# SCH_Bunny-Blinky_2025-12-06.net
KiCad netlist of a schematic drawn in EasyEDA
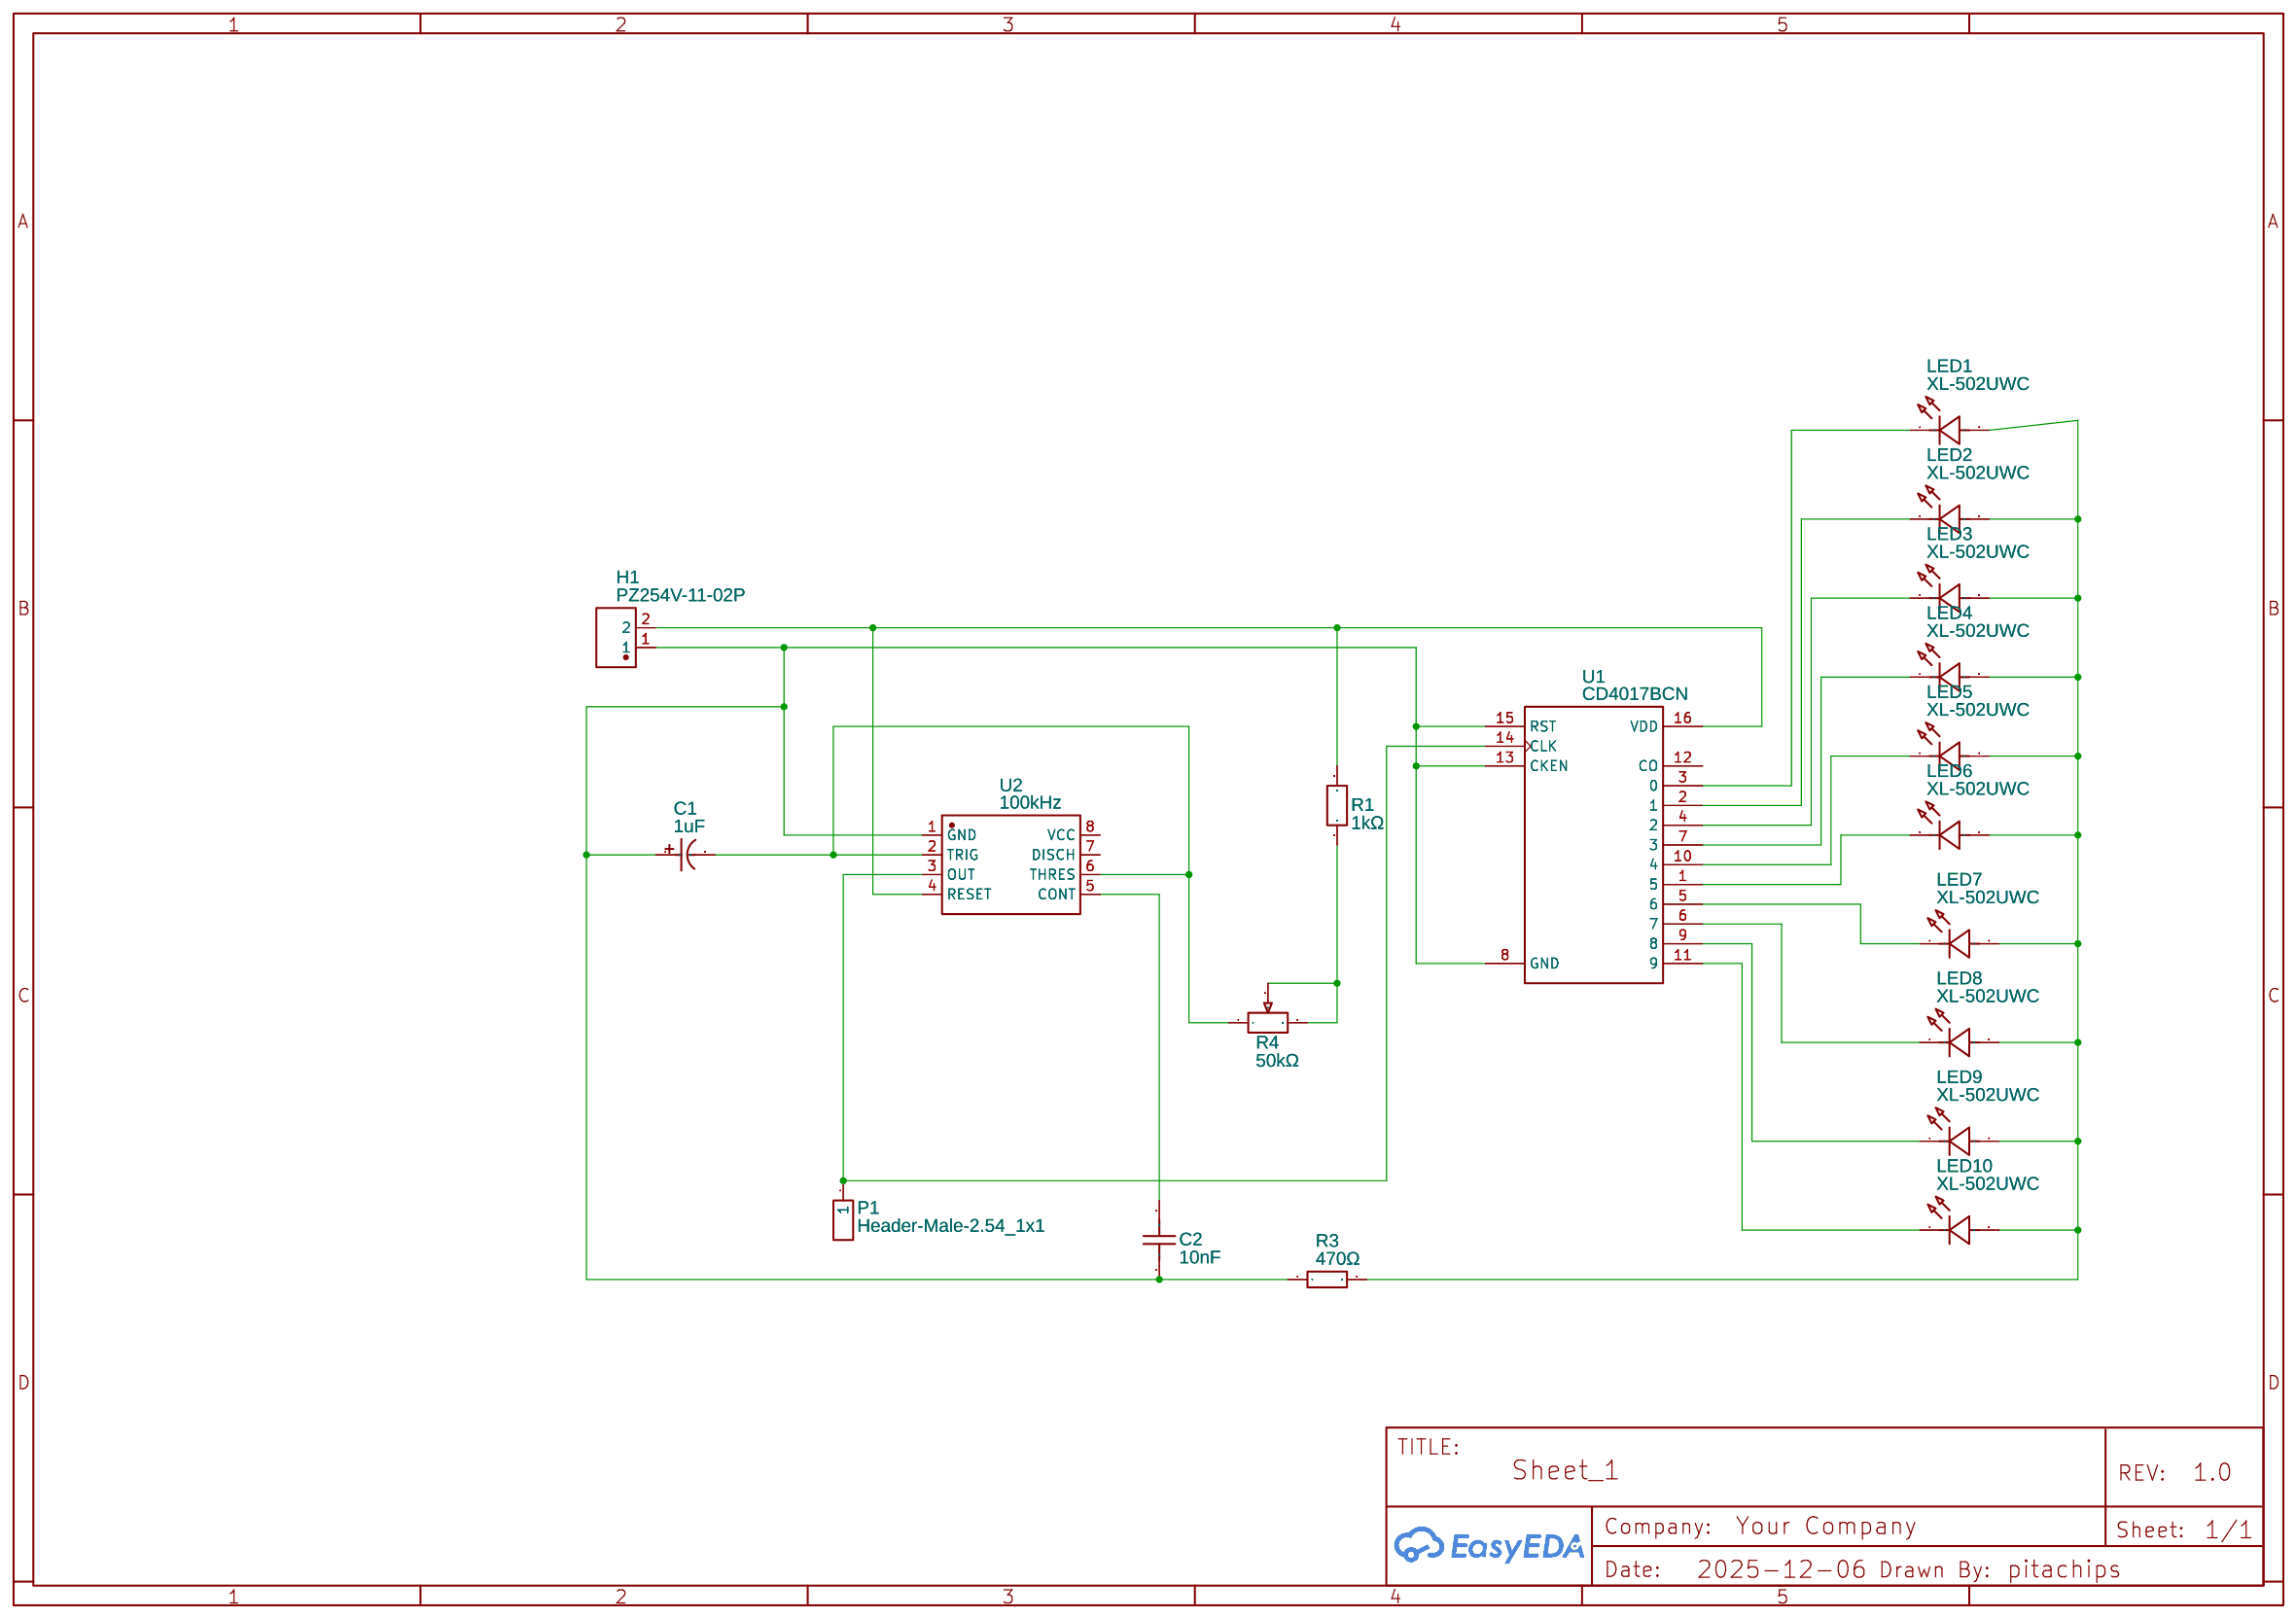
[diagram p0: schematic sheet]

(export (version "E")
  (design (tool "Eeschema 10.0.6"))
  (components
    (comp (ref "C1")
      (value "1uF")
      (fields (field (name "Manufacturer Part") "KF010M050C110A") (field (name "Manufacturer") "CapXon(丰宾)"))
      (libsource (lib "") (part "KF010M050C110A"))
    )
    (comp (ref "C2")
      (value "10nF")
      (fields (field (name "Manufacturer Part") "N09F1B103MN0B0S0N0") (field (name "Manufacturer") "STE(松田)"))
      (libsource (lib "") (part "N09F1B103MN0B0S0N0"))
    )
    (comp (ref "H1")
      (value "PZ254V-11-02P")
      (fields (field (name "Manufacturer") "XFCN(兴飞)"))
      (libsource (lib "") (part "PZ254V-11-02P"))
    )
    (comp (ref "LED1")
      (value "XL-502UWC")
      (fields (field (name "Manufacturer") "XINGLIGHT(成兴光)"))
      (libsource (lib "") (part "XL-502UWC"))
    )
    (comp (ref "LED2")
      (value "XL-502UWC")
      (fields (field (name "Manufacturer") "XINGLIGHT(成兴光)"))
      (libsource (lib "") (part "XL-502UWC"))
    )
    (comp (ref "LED3")
      (value "XL-502UWC")
      (fields (field (name "Manufacturer") "XINGLIGHT(成兴光)"))
      (libsource (lib "") (part "XL-502UWC"))
    )
    (comp (ref "LED4")
      (value "XL-502UWC")
      (fields (field (name "Manufacturer") "XINGLIGHT(成兴光)"))
      (libsource (lib "") (part "XL-502UWC"))
    )
    (comp (ref "LED5")
      (value "XL-502UWC")
      (fields (field (name "Manufacturer") "XINGLIGHT(成兴光)"))
      (libsource (lib "") (part "XL-502UWC"))
    )
    (comp (ref "LED6")
      (value "XL-502UWC")
      (fields (field (name "Manufacturer") "XINGLIGHT(成兴光)"))
      (libsource (lib "") (part "XL-502UWC"))
    )
    (comp (ref "LED7")
      (value "XL-502UWC")
      (fields (field (name "Manufacturer") "XINGLIGHT(成兴光)"))
      (libsource (lib "") (part "XL-502UWC"))
    )
    (comp (ref "LED8")
      (value "XL-502UWC")
      (fields (field (name "Manufacturer") "XINGLIGHT(成兴光)"))
      (libsource (lib "") (part "XL-502UWC"))
    )
    (comp (ref "LED9")
      (value "XL-502UWC")
      (fields (field (name "Manufacturer") "XINGLIGHT(成兴光)"))
      (libsource (lib "") (part "XL-502UWC"))
    )
    (comp (ref "LED10")
      (value "XL-502UWC")
      (fields (field (name "Manufacturer") "XINGLIGHT(成兴光)"))
      (libsource (lib "") (part "XL-502UWC"))
    )
    (comp (ref "P1")
      (value "Header-Male-2.54_1x1")
      (fields (field (name "Manufacturer Part") "2.54-1*1P针") (field (name "Manufacturer") "BOOMELE(博穆精密)"))
      (libsource (lib "") (part "Header-Male-2.54_1x1"))
    )
    (comp (ref "R1")
      (value "1kΩ")
      (fields (field (name "Manufacturer Part") "MF1/4W-1KΩ±1%T52") (field (name "Manufacturer") "华星机电"))
      (libsource (lib "") (part "MF1/4W-1KΩ±1%T52"))
    )
    (comp (ref "R3")
      (value "470Ω")
      (fields
        (field (name "Manufacturer Part") "MFR0W4F4700A50")
        (field (name "Manufacturer") "UNI-ROYAL(厚声)")
      )
      (libsource (lib "") (part "MFR0W4F4700A50"))
    )
    (comp (ref "R4")
      (value "50kΩ")
      (fields (field (name "Manufacturer Part") "3296X-1-503") (field (name "Manufacturer") "BOCHEN(博晨)"))
      (libsource (lib "") (part "3296X-1-503_C118912"))
    )
    (comp (ref "U1") (value "CD4017BCN") (libsource (lib "") (part "CD4017BCN")))
    (comp (ref "U2")
      (value "100kHz")
      (fields (field (name "Manufacturer Part") "NE555P") (field (name "Manufacturer") "TI(德州仪器)"))
      (libsource (lib "") (part "NE555P"))
    )
  )
  (nets
    (net (code "1") (name "Net-(LED1-A)") (class "Default")
      (node (ref "LED1") (pin "2") (pinfunction "A_2") (pintype "unspecified"))
      (node (ref "LED10") (pin "2") (pinfunction "A_2") (pintype "unspecified"))
      (node (ref "LED2") (pin "2") (pinfunction "A_2") (pintype "unspecified"))
      (node (ref "LED3") (pin "2") (pinfunction "A_2") (pintype "unspecified"))
      (node (ref "LED4") (pin "2") (pinfunction "A_2") (pintype "unspecified"))
      (node (ref "LED5") (pin "2") (pinfunction "A_2") (pintype "unspecified"))
      (node (ref "LED6") (pin "2") (pinfunction "A_2") (pintype "unspecified"))
      (node (ref "LED7") (pin "2") (pinfunction "A_2") (pintype "unspecified"))
      (node (ref "LED8") (pin "2") (pinfunction "A_2") (pintype "unspecified"))
      (node (ref "LED9") (pin "2") (pinfunction "A_2") (pintype "unspecified"))
      (node (ref "R3") (pin "2") (pinfunction "2_2") (pintype "input"))
    )
    (net (code "2") (name "Net-(LED1-K)") (class "Default")
      (node (ref "LED1") (pin "1") (pinfunction "K_1") (pintype "unspecified"))
      (node (ref "U1") (pin "3") (pinfunction "0_3") (pintype "output"))
    )
    (net (code "3") (name "Net-(LED2-K)") (class "Default")
      (node (ref "LED2") (pin "1") (pinfunction "K_1") (pintype "unspecified"))
      (node (ref "U1") (pin "2") (pinfunction "1_2") (pintype "output"))
    )
    (net (code "4") (name "Net-(LED3-K)") (class "Default")
      (node (ref "LED3") (pin "1") (pinfunction "K_1") (pintype "unspecified"))
      (node (ref "U1") (pin "4") (pinfunction "2_4") (pintype "output"))
    )
    (net (code "5") (name "Net-(LED4-K)") (class "Default")
      (node (ref "LED4") (pin "1") (pinfunction "K_1") (pintype "unspecified"))
      (node (ref "U1") (pin "7") (pinfunction "3_7") (pintype "output"))
    )
    (net (code "6") (name "Net-(LED5-K)") (class "Default")
      (node (ref "LED5") (pin "1") (pinfunction "K_1") (pintype "unspecified"))
      (node (ref "U1") (pin "10") (pinfunction "4_10") (pintype "output"))
    )
    (net (code "7") (name "Net-(LED6-K)") (class "Default")
      (node (ref "LED6") (pin "1") (pinfunction "K_1") (pintype "unspecified"))
      (node (ref "U1") (pin "1") (pinfunction "5_1") (pintype "output"))
    )
    (net (code "8") (name "Net-(LED7-K)") (class "Default")
      (node (ref "LED7") (pin "1") (pinfunction "K_1") (pintype "unspecified"))
      (node (ref "U1") (pin "5") (pinfunction "6_5") (pintype "output"))
    )
    (net (code "9") (name "Net-(LED8-K)") (class "Default")
      (node (ref "LED8") (pin "1") (pinfunction "K_1") (pintype "unspecified"))
      (node (ref "U1") (pin "6") (pinfunction "7_6") (pintype "output"))
    )
    (net (code "10") (name "Net-(LED9-K)") (class "Default")
      (node (ref "LED9") (pin "1") (pinfunction "K_1") (pintype "unspecified"))
      (node (ref "U1") (pin "9") (pinfunction "8_9") (pintype "output"))
    )
    (net (code "11") (name "Net-(LED10-K)") (class "Default")
      (node (ref "LED10") (pin "1") (pinfunction "K_1") (pintype "unspecified"))
      (node (ref "U1") (pin "11") (pinfunction "9_11") (pintype "output"))
    )
    (net (code "12") (name "Net-(R1-Pad1)") (class "Default")
      (node (ref "R1") (pin "1") (pinfunction "1_1") (pintype "unspecified"))
      (node (ref "R4") (pin "2") (pinfunction "2_2") (pintype "input"))
      (node (ref "R4") (pin "3") (pinfunction "3_3") (pintype "input"))
    )
    (net (code "13") (name "Net-(U1-CKEN)") (class "Default")
      (node (ref "C1") (pin "1") (pinfunction "1_1") (pintype "input"))
      (node (ref "C2") (pin "1") (pinfunction "1_1") (pintype "unspecified"))
      (node (ref "H1") (pin "1") (pinfunction "1_1") (pintype "unspecified"))
      (node (ref "R3") (pin "1") (pinfunction "1_1") (pintype "input"))
      (node (ref "U1") (pin "13") (pinfunction "CKEN_13") (pintype "unspecified"))
      (node (ref "U1") (pin "15") (pinfunction "RST_15") (pintype "unspecified"))
      (node (ref "U1") (pin "8") (pinfunction "GND_8") (pintype "passive"))
      (node (ref "U2") (pin "1") (pinfunction "GND_1") (pintype "unspecified"))
    )
    (net (code "14") (name "Net-(U1-CLK)") (class "Default")
      (node (ref "P1") (pin "1") (pinfunction "1_1") (pintype "input"))
      (node (ref "U1") (pin "14") (pinfunction "CLK_14") (pintype "unspecified"))
      (node (ref "U2") (pin "3") (pinfunction "OUT_3") (pintype "unspecified"))
    )
    (net (code "15") (name "Net-(U1-VDD)") (class "Default")
      (node (ref "H1") (pin "2") (pinfunction "2_2") (pintype "unspecified"))
      (node (ref "R1") (pin "2") (pinfunction "2_2") (pintype "unspecified"))
      (node (ref "U1") (pin "16") (pinfunction "VDD_16") (pintype "passive"))
      (node (ref "U2") (pin "4") (pinfunction "RESET_4") (pintype "unspecified"))
    )
    (net (code "16") (name "Net-(U2-CONT)") (class "Default")
      (node (ref "C2") (pin "2") (pinfunction "2_2") (pintype "unspecified"))
      (node (ref "U2") (pin "5") (pinfunction "CONT_5") (pintype "unspecified"))
    )
    (net (code "17") (name "Net-(U2-THRES)") (class "Default")
      (node (ref "C1") (pin "2") (pinfunction "2_2") (pintype "input"))
      (node (ref "R4") (pin "1") (pinfunction "1_1") (pintype "input"))
      (node (ref "U2") (pin "2") (pinfunction "TRIG_2") (pintype "unspecified"))
      (node (ref "U2") (pin "6") (pinfunction "THRES_6") (pintype "unspecified"))
    )
    (net (code "18") (name "unconnected-(U1-CO-Pad12)") (class "Default")
      (node (ref "U1") (pin "12") (pinfunction "CO_12") (pintype "output"))
    )
    (net (code "19") (name "unconnected-(U2-DISCH-Pad7)") (class "Default")
      (node (ref "U2") (pin "7") (pinfunction "DISCH_7") (pintype "unspecified"))
    )
    (net (code "20") (name "unconnected-(U2-VCC-Pad8)") (class "Default")
      (node (ref "U2") (pin "8") (pinfunction "VCC_8") (pintype "unspecified"))
    )
  )
)
